# Input.net
KiCad netlist of a schematic drawn in Altium Designer
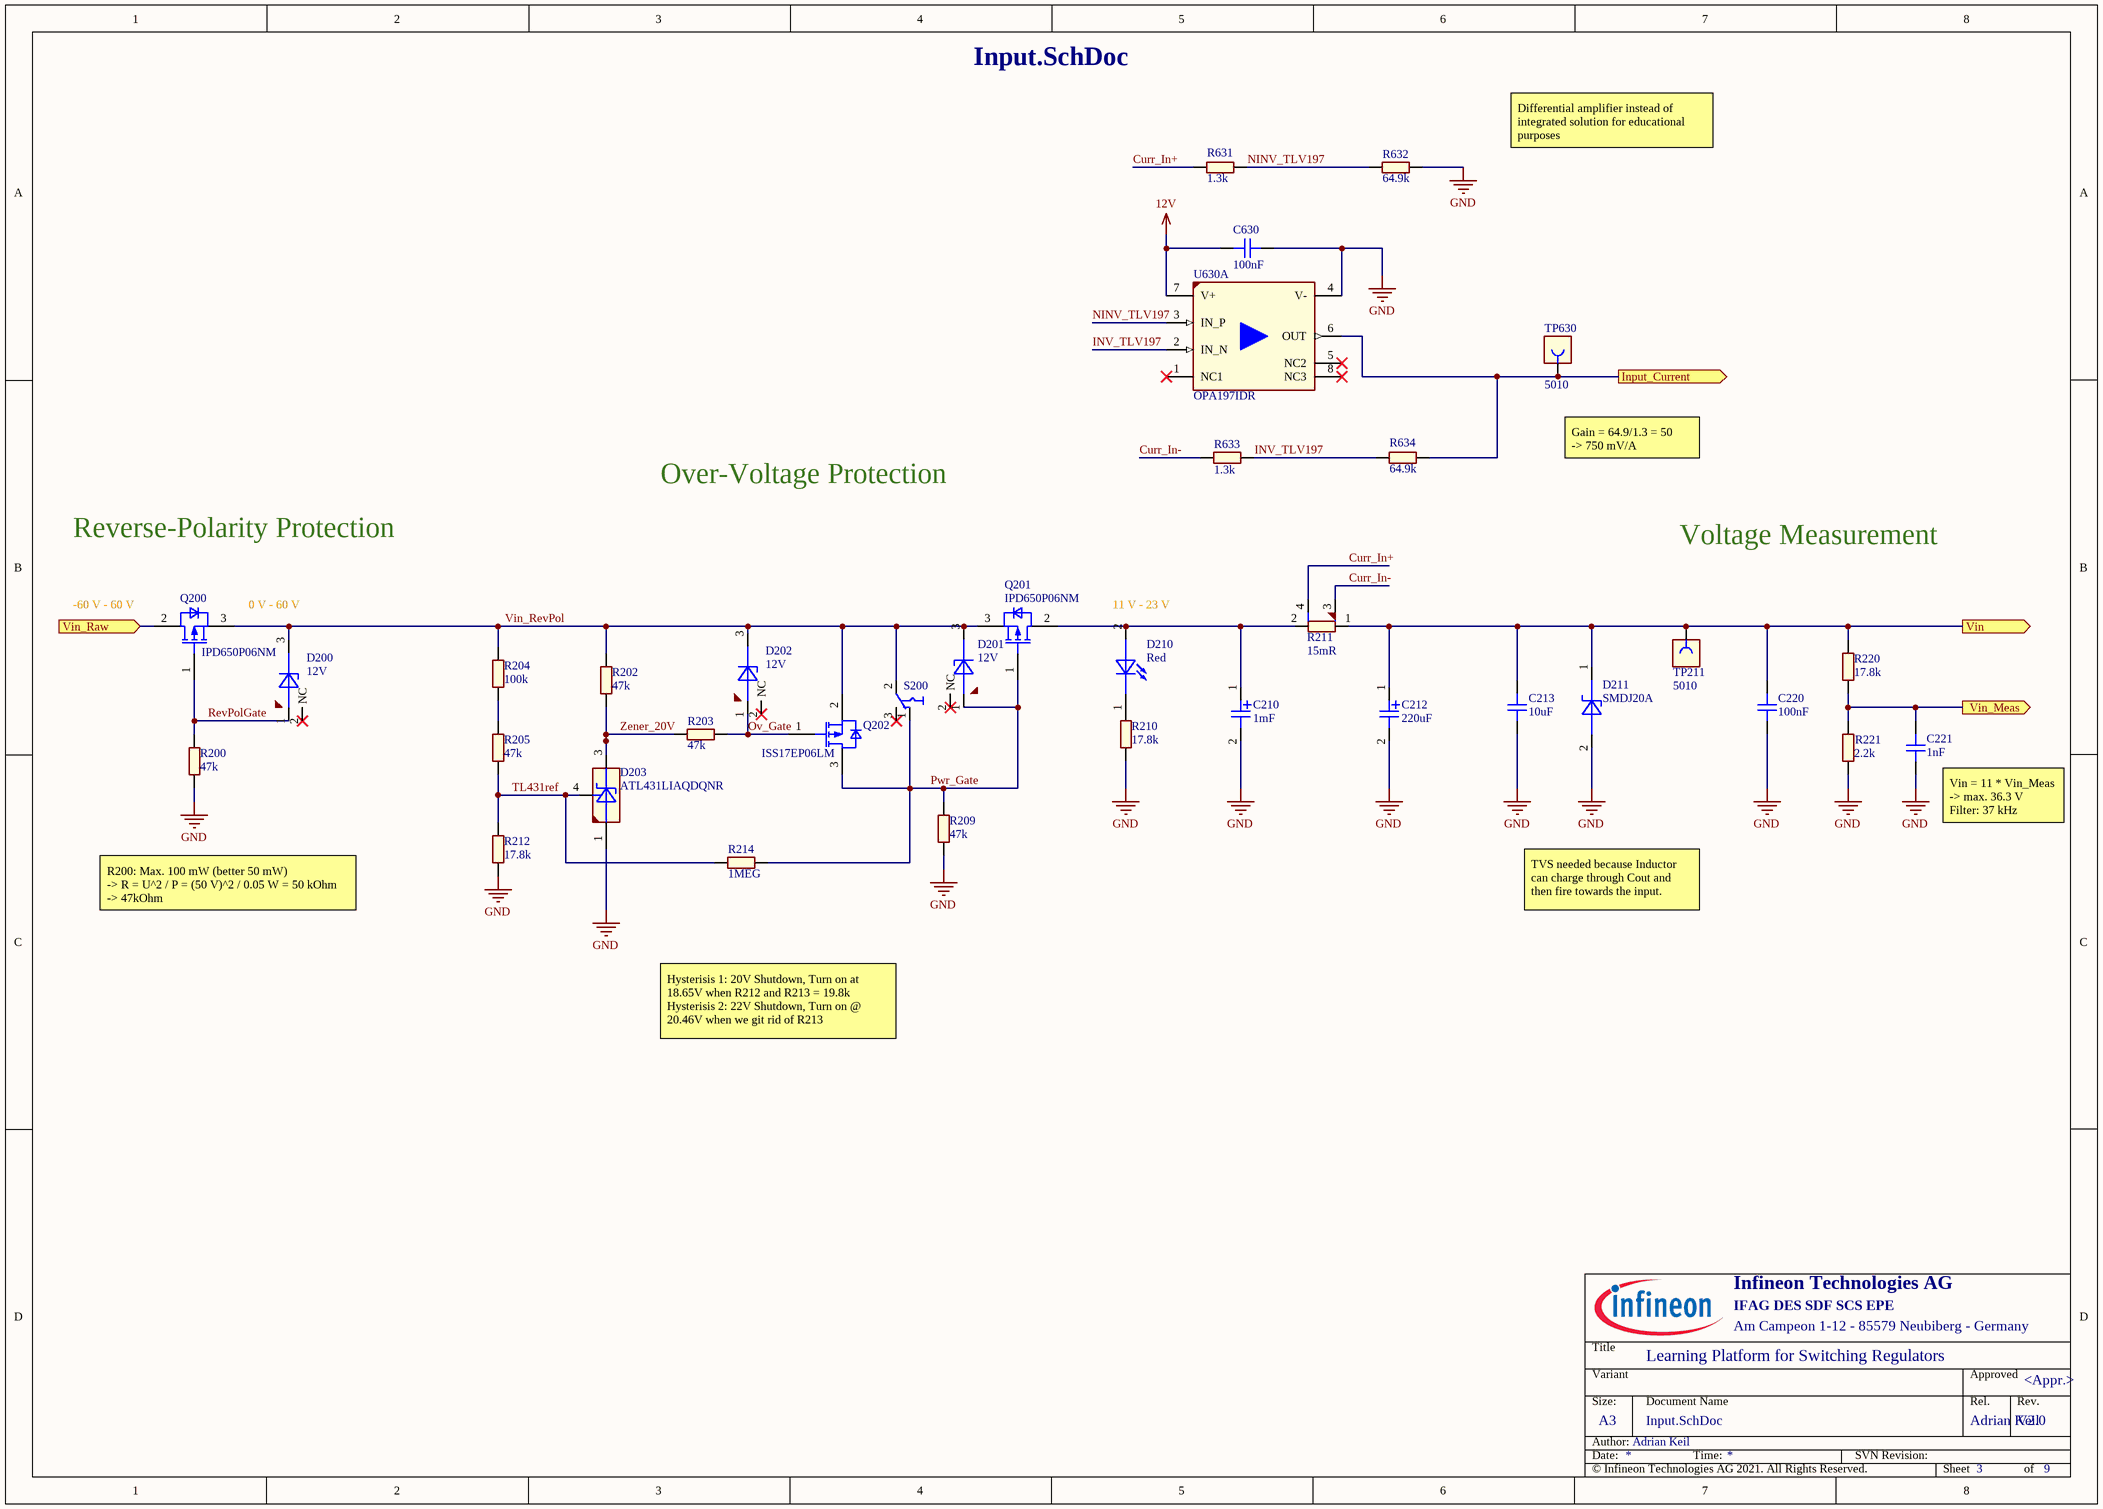
[diagram p0: Input.SchDoc]

(export (version "E")
  (design (tool "Eeschema 10.0.6"))
  (components
    (comp (ref "C210")
      (value "1mF")
      (footprint "CAPPRD500W60D1300H2700B")
      (fields (field (name "MANUFACTURER") "Kemet"))
      (libsource (lib "PCBLibraryData") (part "CAP-SGL-POL-02P_00000002"))
    )
    (comp (ref "C212")
      (value "220uF")
      (footprint "CAPAE1030X1050N-3")
      (fields (field (name "MANUFACTURER") "Nippon Chemi-Con"))
      (libsource (lib "PCBLibraryData") (part "CAP-SGL-POL-02P_00000002"))
    )
    (comp (ref "C213")
      (value "10uF")
      (footprint "CAPC3216X190N-1")
      (description "CAP / CERA / 10uF / 50V / 20% / X5R (EIA) / -55°C to 85°C / 1206 (3216) / SMD / -")
      (fields (field (name "MANUFACTURER") "Taiyo Yuden"))
      (libsource (lib "PCBLibraryData") (part "CAP-SGL-STD-02P_00000001"))
    )
    (comp (ref "C220")
      (value "100nF")
      (footprint "CAPC1608X90N-2")
      (description "CAP / CERA / 100nF / 50V / 10% / X7R (EIA) / -55°C to 125°C / 0603 / SMD / -")
      (fields (field (name "MANUFACTURER") "AVX"))
      (libsource (lib "PCBLibraryData") (part "CAP-SGL-STD-02P_00000001"))
    )
    (comp (ref "C221")
      (value "1nF")
      (footprint "CAPC1608X87N-1")
      (description "CAP / CERA / 1nF / 50V / 10% / X7R (EIA) / -55°C to 125°C / 0603 (1608) / SMD / -")
      (fields (field (name "MANUFACTURER") "Wurth Elektronik"))
      (libsource (lib "PCBLibraryData") (part "CAP-SGL-STD-02P_00000001"))
    )
    (comp (ref "C630")
      (value "100nF")
      (footprint "CAPC1608X90N-2")
      (description "CAP / CERA / 100nF / 50V / 10% / X7R (EIA) / -55°C to 125°C / 0603 / SMD / -")
      (fields (field (name "MANUFACTURER") "AVX"))
      (libsource (lib "PCBLibraryData") (part "CAP-SGL-STD-02P_00000001"))
    )
    (comp (ref "D200")
      (value "12V")
      (footprint "SOT95P230X110-3N")
      (description "Voltage regulator diodes")
      (fields (field (name "MANUFACTURER") "Nexperia"))
      (libsource (lib "PCBLibraryData") (part "d_zener_a1c3_3p"))
    )
    (comp (ref "D201")
      (value "12V")
      (footprint "SOT95P230X110-3N")
      (description "Voltage regulator diodes")
      (fields (field (name "MANUFACTURER") "Nexperia"))
      (libsource (lib "PCBLibraryData") (part "d_zener_a1c3_3p"))
    )
    (comp (ref "D202")
      (value "12V")
      (footprint "SOT95P230X110-3N")
      (description "Voltage regulator diodes")
      (fields (field (name "MANUFACTURER") "Nexperia"))
      (libsource (lib "PCBLibraryData") (part "d_zener_a1c3_3p"))
    )
    (comp (ref "D203")
      (value "ATL431LIAQDQNR")
      (footprint "TI-SMD-X2SON-V")
      (description "High Bandwidth Low-Iq Programmable Shunt Regulator")
      (fields (field (name "MANUFACTURER") "Texas Instruments"))
      (libsource (lib "PCBLibraryData") (part "ATL431LIXXDQNX"))
    )
    (comp (ref "D210")
      (value "Red")
      (footprint "LEDSC160X80X80-2N-1")
      (description "WL-SMCW SMT Mono-color Chip LED Waterclear, Red,630nm")
      (fields (field (name "MANUFACTURER") "Wurth Elektronik"))
      (libsource (lib "PCBLibraryData") (part "d_led_a"))
    )
    (comp (ref "D211")
      (value "SMDJ20A")
      (footprint "DIOM7959X262N")
      (description "TVS Diode, Low Profile Package, Built in Strain Relief, Glass Passivated Chip Junction")
      (fields (field (name "MANUFACTURER") "Littelfuse"))
      (libsource (lib "PCBLibraryData") (part "d_tvs_a"))
    )
    (comp (ref "Q200")
      (value "IPD650P06NM")
      (footprint "TO228P998X250-3N-V2")
      (description "OptiMOS Power Transistor, -60 V")
      (fields (field (name "MANUFACTURER") "Infineon Technologies"))
      (libsource (lib "PCBLibraryData") (part "igfet_p_ch_enh_dio_1g2d3s_3p"))
    )
    (comp (ref "Q201")
      (value "IPD650P06NM")
      (footprint "TO228P998X250-3N-V2")
      (description "OptiMOS Power Transistor, -60 V")
      (fields (field (name "MANUFACTURER") "Infineon Technologies"))
      (libsource (lib "PCBLibraryData") (part "igfet_p_ch_enh_dio_1g2d3s_3p"))
    )
    (comp (ref "Q202")
      (value "ISS17EP06LM")
      (footprint "SOT95P240X110-3N-1-V")
      (description "OptiMOSTM Small Signal Transistor, -60 V")
      (fields (field (name "MANUFACTURER") "Infineon Technologies"))
      (libsource (lib "PCBLibraryData") (part "igfet_p_ch_enh_dio_1g2s3d_3p"))
    )
    (comp (ref "R200")
      (value "47k")
      (footprint "RESC1609X50N")
      (description "RES / STD / 47k / 100mW / 1% / 100ppm/K / -55°C to 155°C / 0603 / SMD / -")
      (fields (field (name "LEGACY PARTNUMBER") "RES01801333") (field (name "MANUFACTURER") "Vishay"))
      (libsource (lib "") (part "RES-SGL-STD-02P_00000006_2"))
    )
    (comp (ref "R202")
      (value "47k")
      (footprint "RESC1609X50N")
      (description "RES / STD / 47k / 100mW / 1% / 100ppm/K / -55°C to 155°C / 0603 / SMD / -")
      (fields (field (name "LEGACY PARTNUMBER") "RES01801333") (field (name "MANUFACTURER") "Vishay"))
      (libsource (lib "") (part "RES-SGL-STD-02P_00000006_2"))
    )
    (comp (ref "R203")
      (value "47k")
      (footprint "RESC1609X50N")
      (description "RES / STD / 47k / 100mW / 1% / 100ppm/K / -55°C to 155°C / 0603 / SMD / -")
      (fields (field (name "LEGACY PARTNUMBER") "RES01801333") (field (name "MANUFACTURER") "Vishay"))
      (libsource (lib "") (part "RES-SGL-STD-02P_00000006_3"))
    )
    (comp (ref "R204")
      (value "100k")
      (footprint "RESC1508X60N")
      (fields (field (name "MANUFACTURER") "Bourns"))
      (libsource (lib "PCBLibraryData") (part "RES-SGL-STD-02P_00000006"))
    )
    (comp (ref "R205")
      (value "47k")
      (footprint "RESC1609X50N")
      (description "RES / STD / 47k / 100mW / 1% / 100ppm/K / -55°C to 155°C / 0603 / SMD / -")
      (fields (field (name "LEGACY PARTNUMBER") "RES01801333") (field (name "MANUFACTURER") "Vishay"))
      (libsource (lib "") (part "RES-SGL-STD-02P_00000006_2"))
    )
    (comp (ref "R209")
      (value "47k")
      (footprint "RESC1609X50N")
      (description "RES / STD / 47k / 100mW / 1% / 100ppm/K / -55°C to 155°C / 0603 / SMD / -")
      (fields (field (name "LEGACY PARTNUMBER") "RES01801333") (field (name "MANUFACTURER") "Vishay"))
      (libsource (lib "") (part "RES-SGL-STD-02P_00000006_2"))
    )
    (comp (ref "R210")
      (value "17.8k")
      (footprint "RESC1608X60N")
      (fields (field (name "MANUFACTURER") "Multicomp"))
      (libsource (lib "PCBLibraryData") (part "RES-SGL-STD-02P_00000006"))
    )
    (comp (ref "R211")
      (value "15mR")
      (footprint "RES-SMD-L4T12")
      (description "RES / STD / 15mR / 500mW / 1% / 75ppm/K / -55°C to 155°C / 1206 (3216) / SMD / -")
      (fields (field (name "MANUFACTURER") "Ohmite"))
      (libsource (lib "PCBLibraryData") (part "RES-SHT-STD-04P_00097BE5"))
    )
    (comp (ref "R212")
      (value "17.8k")
      (footprint "RESC1608X60N")
      (fields (field (name "MANUFACTURER") "Multicomp"))
      (libsource (lib "PCBLibraryData") (part "RES-SGL-STD-02P_00000006"))
    )
    (comp (ref "R214")
      (value "1MEG")
      (footprint "RESC1608X55N-0")
      (description "RES / STD / 1MEG / 63mW / 1% / 100ppm/K / - / 1.60mm L X 0.825mm W X 0.55mm H / - / -")
      (fields (field (name "MANUFACTURER") "Multicomp"))
      (libsource (lib "") (part "RES-SGL-STD-02P_00000006_1"))
    )
    (comp (ref "R220")
      (value "17.8k")
      (footprint "RESC1608X60N")
      (fields (field (name "MANUFACTURER") "Multicomp"))
      (libsource (lib "PCBLibraryData") (part "RES-SGL-STD-02P_00000006"))
    )
    (comp (ref "R221")
      (value "2.2k")
      (footprint "RESC1609X50N")
      (description "RES / STD / 2.2k / 100mW / 1% / 100ppm/K / -55°C to 155°C / 0603 / SMD / -")
      (fields (field (name "LEGACY PARTNUMBER") "RES01801179") (field (name "MANUFACTURER") "Vishay"))
      (libsource (lib "PCBLibraryData") (part "RES-SGL-STD-02P_00000006"))
    )
    (comp (ref "R631")
      (value "1.3k")
      (footprint "RESC1608X60N")
      (description "RES / STD / 1.3k / 100mW / 1% / 100ppm/K / -55°C to 155°C / 1.60mm L X 0.80mm W X 0.60mm H / - / -")
      (fields (field (name "MANUFACTURER") "Multicomp"))
      (libsource (lib "") (part "RES-SGL-STD-02P_00000006_1"))
    )
    (comp (ref "R632")
      (value "64.9k")
      (footprint "RESC1608X60N")
      (fields (field (name "MANUFACTURER") "Multicomp"))
      (libsource (lib "") (part "RES-SGL-STD-02P_00000006_1"))
    )
    (comp (ref "R633")
      (value "1.3k")
      (footprint "RESC1608X60N")
      (description "RES / STD / 1.3k / 100mW / 1% / 100ppm/K / -55°C to 155°C / 1.60mm L X 0.80mm W X 0.60mm H / - / -")
      (fields (field (name "MANUFACTURER") "Multicomp"))
      (libsource (lib "") (part "RES-SGL-STD-02P_00000006_1"))
    )
    (comp (ref "R634")
      (value "64.9k")
      (footprint "RESC1608X60N")
      (fields (field (name "MANUFACTURER") "Multicomp"))
      (libsource (lib "") (part "RES-SGL-STD-02P_00000006_1"))
    )
    (comp (ref "S200")
      (value "CL-SB-12A-01T")
      (footprint "SW-SMD-CL-SB-12A-01T")
      (description "Slid Switch, 12V, 200mA")
      (fields (field (name "MANUFACTURER") "NIDEC COPAL ELECTRONICS, Inc."))
      (libsource (lib "PCBLibraryData") (part "sw_co213_3p"))
    )
    (comp (ref "TP211")
      (value "5010")
      (footprint "CON-THT-TP-5010")
      (description "PC Test Point-Multipurpose THT, Red")
      (fields
        (field (name "LEGACY PARTNUMBER") "CON01500529")
        (field (name "MANUFACTURER") "Keystone Electronics Corp.")
      )
      (libsource (lib "PCBLibraryData") (part "connector_1_f"))
    )
    (comp (ref "TP630")
      (value "5010")
      (footprint "CON-THT-TP-5010")
      (description "PC Test Point-Multipurpose THT, Red")
      (fields
        (field (name "LEGACY PARTNUMBER") "CON01500529")
        (field (name "MANUFACTURER") "Keystone Electronics Corp.")
      )
      (libsource (lib "") (part "connector_1_f_1"))
    )
    (comp (ref "U630")
      (value "OPA197IDR")
      (footprint "SOIC127P600X175-8N-23")
      (fields (field (name "MANUFACTURER") "Texas Instruments"))
      (libsource (lib "PCBLibraryData") (part "OPA140AID"))
    )
  )
  (nets
    (net (code "1") (name "/Curr_In+") (class "Default")
      (node (ref "R211") (pin "4") (pinfunction "I2_4") (pintype "passive"))
      (node (ref "R631") (pin "1") (pinfunction "1_1") (pintype "passive"))
    )
    (net (code "2") (name "/Curr_In-") (class "Default")
      (node (ref "R211") (pin "3") (pinfunction "I1_3") (pintype "passive"))
      (node (ref "R633") (pin "1") (pinfunction "1_1") (pintype "passive"))
    )
    (net (code "3") (name "/INV_TLV197") (class "Default")
      (node (ref "R633") (pin "2") (pinfunction "2_2") (pintype "passive"))
      (node (ref "R634") (pin "1") (pinfunction "1_1") (pintype "passive"))
      (node (ref "U630") (pin "2") (pinfunction "IN_N_2") (pintype "input"))
    )
    (net (code "4") (name "/Input_Current") (class "Default")
      (node (ref "R634") (pin "2") (pinfunction "2_2") (pintype "passive"))
      (node (ref "TP630") (pin "1") (pinfunction "1_1") (pintype "passive"))
      (node (ref "U630") (pin "6") (pinfunction "OUT_6") (pintype "output"))
    )
    (net (code "5") (name "/NINV_TLV197") (class "Default")
      (node (ref "R631") (pin "2") (pinfunction "2_2") (pintype "passive"))
      (node (ref "R632") (pin "1") (pinfunction "1_1") (pintype "passive"))
      (node (ref "U630") (pin "3") (pinfunction "IN_P_3") (pintype "input"))
    )
    (net (code "6") (name "/Ov_Gate") (class "Default")
      (node (ref "D202") (pin "1") (pinfunction "ANODE_1") (pintype "passive"))
      (node (ref "Q202") (pin "1") (pinfunction "GATE_1") (pintype "passive"))
      (node (ref "R203") (pin "1") (pinfunction "1_1") (pintype "passive"))
    )
    (net (code "7") (name "/Pwr_Gate") (class "Default")
      (node (ref "D201") (pin "1") (pinfunction "ANODE_1") (pintype "passive"))
      (node (ref "Q201") (pin "1") (pinfunction "GATE_1") (pintype "passive"))
      (node (ref "Q202") (pin "3") (pinfunction "DRAIN_3") (pintype "passive"))
      (node (ref "R209") (pin "2") (pinfunction "2_2") (pintype "passive"))
      (node (ref "R214") (pin "2") (pinfunction "2_2") (pintype "passive"))
      (node (ref "S200") (pin "1") (pinfunction "1_1") (pintype "passive"))
    )
    (net (code "8") (name "/RevPolGate") (class "Default")
      (node (ref "D200") (pin "1") (pinfunction "ANODE_1") (pintype "passive"))
      (node (ref "Q200") (pin "1") (pinfunction "GATE_1") (pintype "passive"))
      (node (ref "R200") (pin "2") (pinfunction "2_2") (pintype "passive"))
    )
    (net (code "9") (name "/TL431ref") (class "Default")
      (node (ref "D203") (pin "4") (pinfunction "REF_4") (pintype "passive"))
      (node (ref "R205") (pin "1") (pinfunction "1_1") (pintype "passive"))
      (node (ref "R212") (pin "1") (pinfunction "1_1") (pintype "passive"))
      (node (ref "R214") (pin "1") (pinfunction "1_1") (pintype "passive"))
    )
    (net (code "10") (name "/Vin") (class "Default")
      (node (ref "C212") (pin "1") (pinfunction "1_1") (pintype "passive"))
      (node (ref "C213") (pin "2") (pinfunction "2_2") (pintype "passive"))
      (node (ref "C220") (pin "1") (pinfunction "1_1") (pintype "passive"))
      (node (ref "D211") (pin "1") (pinfunction "CATHODE_1") (pintype "passive"))
      (node (ref "R211") (pin "1") (pinfunction "V1_1") (pintype "passive"))
      (node (ref "R220") (pin "1") (pinfunction "1_1") (pintype "passive"))
      (node (ref "TP211") (pin "1") (pinfunction "1_1") (pintype "passive"))
    )
    (net (code "11") (name "/Vin_Meas") (class "Default")
      (node (ref "C221") (pin "2") (pinfunction "2_2") (pintype "passive"))
      (node (ref "R220") (pin "2") (pinfunction "2_2") (pintype "passive"))
      (node (ref "R221") (pin "1") (pinfunction "1_1") (pintype "passive"))
    )
    (net (code "12") (name "/Vin_Raw") (class "Default")
      (node (ref "Q200") (pin "2") (pinfunction "DRAIN_2") (pintype "passive"))
    )
    (net (code "13") (name "/Vin_RevPol") (class "Default")
      (node (ref "D200") (pin "3") (pinfunction "CATHODE_3") (pintype "passive"))
      (node (ref "D201") (pin "3") (pinfunction "CATHODE_3") (pintype "passive"))
      (node (ref "D202") (pin "3") (pinfunction "CATHODE_3") (pintype "passive"))
      (node (ref "Q200") (pin "3") (pinfunction "SOURCE_3") (pintype "passive"))
      (node (ref "Q201") (pin "3") (pinfunction "SOURCE_3") (pintype "passive"))
      (node (ref "Q202") (pin "2") (pinfunction "SOURCE_2") (pintype "passive"))
      (node (ref "R202") (pin "2") (pinfunction "2_2") (pintype "passive"))
      (node (ref "R204") (pin "1") (pinfunction "1_1") (pintype "passive"))
      (node (ref "S200") (pin "2") (pinfunction "2_2") (pintype "passive"))
    )
    (net (code "14") (name "/Zener_20V") (class "Default")
      (node (ref "D203") (pin "3") (pinfunction "C_3") (pintype "passive"))
      (node (ref "R202") (pin "1") (pinfunction "1_1") (pintype "passive"))
      (node (ref "R203") (pin "2") (pinfunction "2_2") (pintype "passive"))
    )
    (net (code "15") (name "12V") (class "Default")
      (node (ref "C630") (pin "2") (pinfunction "2_2") (pintype "passive"))
      (node (ref "U630") (pin "7") (pinfunction "V+_7") (pintype "power_in"))
    )
    (net (code "16") (name "EP") (class "Default")
      (node (ref "D203") (pin "5") (pinfunction "EP_5") (pintype "power_in"))
    )
    (net (code "17") (name "GND") (class "Default")
      (node (ref "C210") (pin "2") (pinfunction "2_2") (pintype "passive"))
      (node (ref "C212") (pin "2") (pinfunction "2_2") (pintype "passive"))
      (node (ref "C213") (pin "1") (pinfunction "1_1") (pintype "passive"))
      (node (ref "C220") (pin "2") (pinfunction "2_2") (pintype "passive"))
      (node (ref "C221") (pin "1") (pinfunction "1_1") (pintype "passive"))
      (node (ref "C630") (pin "1") (pinfunction "1_1") (pintype "passive"))
      (node (ref "D203") (pin "1") (pinfunction "A_1") (pintype "passive"))
      (node (ref "D211") (pin "2") (pinfunction "ANODE_2") (pintype "passive"))
      (node (ref "R200") (pin "1") (pinfunction "1_1") (pintype "passive"))
      (node (ref "R209") (pin "1") (pinfunction "1_1") (pintype "passive"))
      (node (ref "R210") (pin "2") (pinfunction "2_2") (pintype "passive"))
      (node (ref "R212") (pin "2") (pinfunction "2_2") (pintype "passive"))
      (node (ref "R221") (pin "2") (pinfunction "2_2") (pintype "passive"))
      (node (ref "R632") (pin "2") (pinfunction "2_2") (pintype "passive"))
      (node (ref "U630") (pin "4") (pinfunction "V-_4") (pintype "power_in"))
    )
    (net (code "18") (name "Net-(D210-Anode)") (class "Default")
      (node (ref "C210") (pin "1") (pinfunction "1_1") (pintype "passive"))
      (node (ref "D210") (pin "2") (pinfunction "Anode_2") (pintype "passive"))
      (node (ref "Q201") (pin "2") (pinfunction "DRAIN_2") (pintype "passive"))
      (node (ref "R211") (pin "2") (pinfunction "V2_2") (pintype "passive"))
    )
    (net (code "19") (name "Net-(D210-Cathode)") (class "Default")
      (node (ref "D210") (pin "1") (pinfunction "Cathode_1") (pintype "passive"))
      (node (ref "R210") (pin "1") (pinfunction "1_1") (pintype "passive"))
    )
    (net (code "20") (name "Net-(R204-Pad2)") (class "Default")
      (node (ref "R204") (pin "2") (pinfunction "2_2") (pintype "passive"))
      (node (ref "R205") (pin "2") (pinfunction "2_2") (pintype "passive"))
    )
    (net (code "21") (name "unconnected-(D200-NC-Pad2)") (class "Default")
      (node (ref "D200") (pin "2") (pinfunction "NC_2") (pintype "passive+no_connect"))
    )
    (net (code "22") (name "unconnected-(D201-NC-Pad2)") (class "Default")
      (node (ref "D201") (pin "2") (pinfunction "NC_2") (pintype "passive+no_connect"))
    )
    (net (code "23") (name "unconnected-(D202-NC-Pad2)") (class "Default")
      (node (ref "D202") (pin "2") (pinfunction "NC_2") (pintype "passive+no_connect"))
    )
    (net (code "24") (name "unconnected-(D203-NC-Pad2)") (class "Default")
      (node (ref "D203") (pin "2") (pinfunction "NC_2") (pintype "passive"))
    )
    (net (code "25") (name "unconnected-(S200-Pad3)") (class "Default")
      (node (ref "S200") (pin "3") (pinfunction "3_3") (pintype "passive+no_connect"))
    )
    (net (code "26") (name "unconnected-(U630-NC1-Pad1)") (class "Default")
      (node (ref "U630") (pin "1") (pinfunction "NC1_1") (pintype "passive+no_connect"))
    )
    (net (code "27") (name "unconnected-(U630-NC2-Pad5)") (class "Default")
      (node (ref "U630") (pin "5") (pinfunction "NC2_5") (pintype "passive+no_connect"))
    )
    (net (code "28") (name "unconnected-(U630-NC3-Pad8)") (class "Default")
      (node (ref "U630") (pin "8") (pinfunction "NC3_8") (pintype "passive+no_connect"))
    )
  )
)
